# Adafruit_128x64_Mono_OLED_PCB_v2.net
KiCad netlist of a schematic drawn in EAGLE
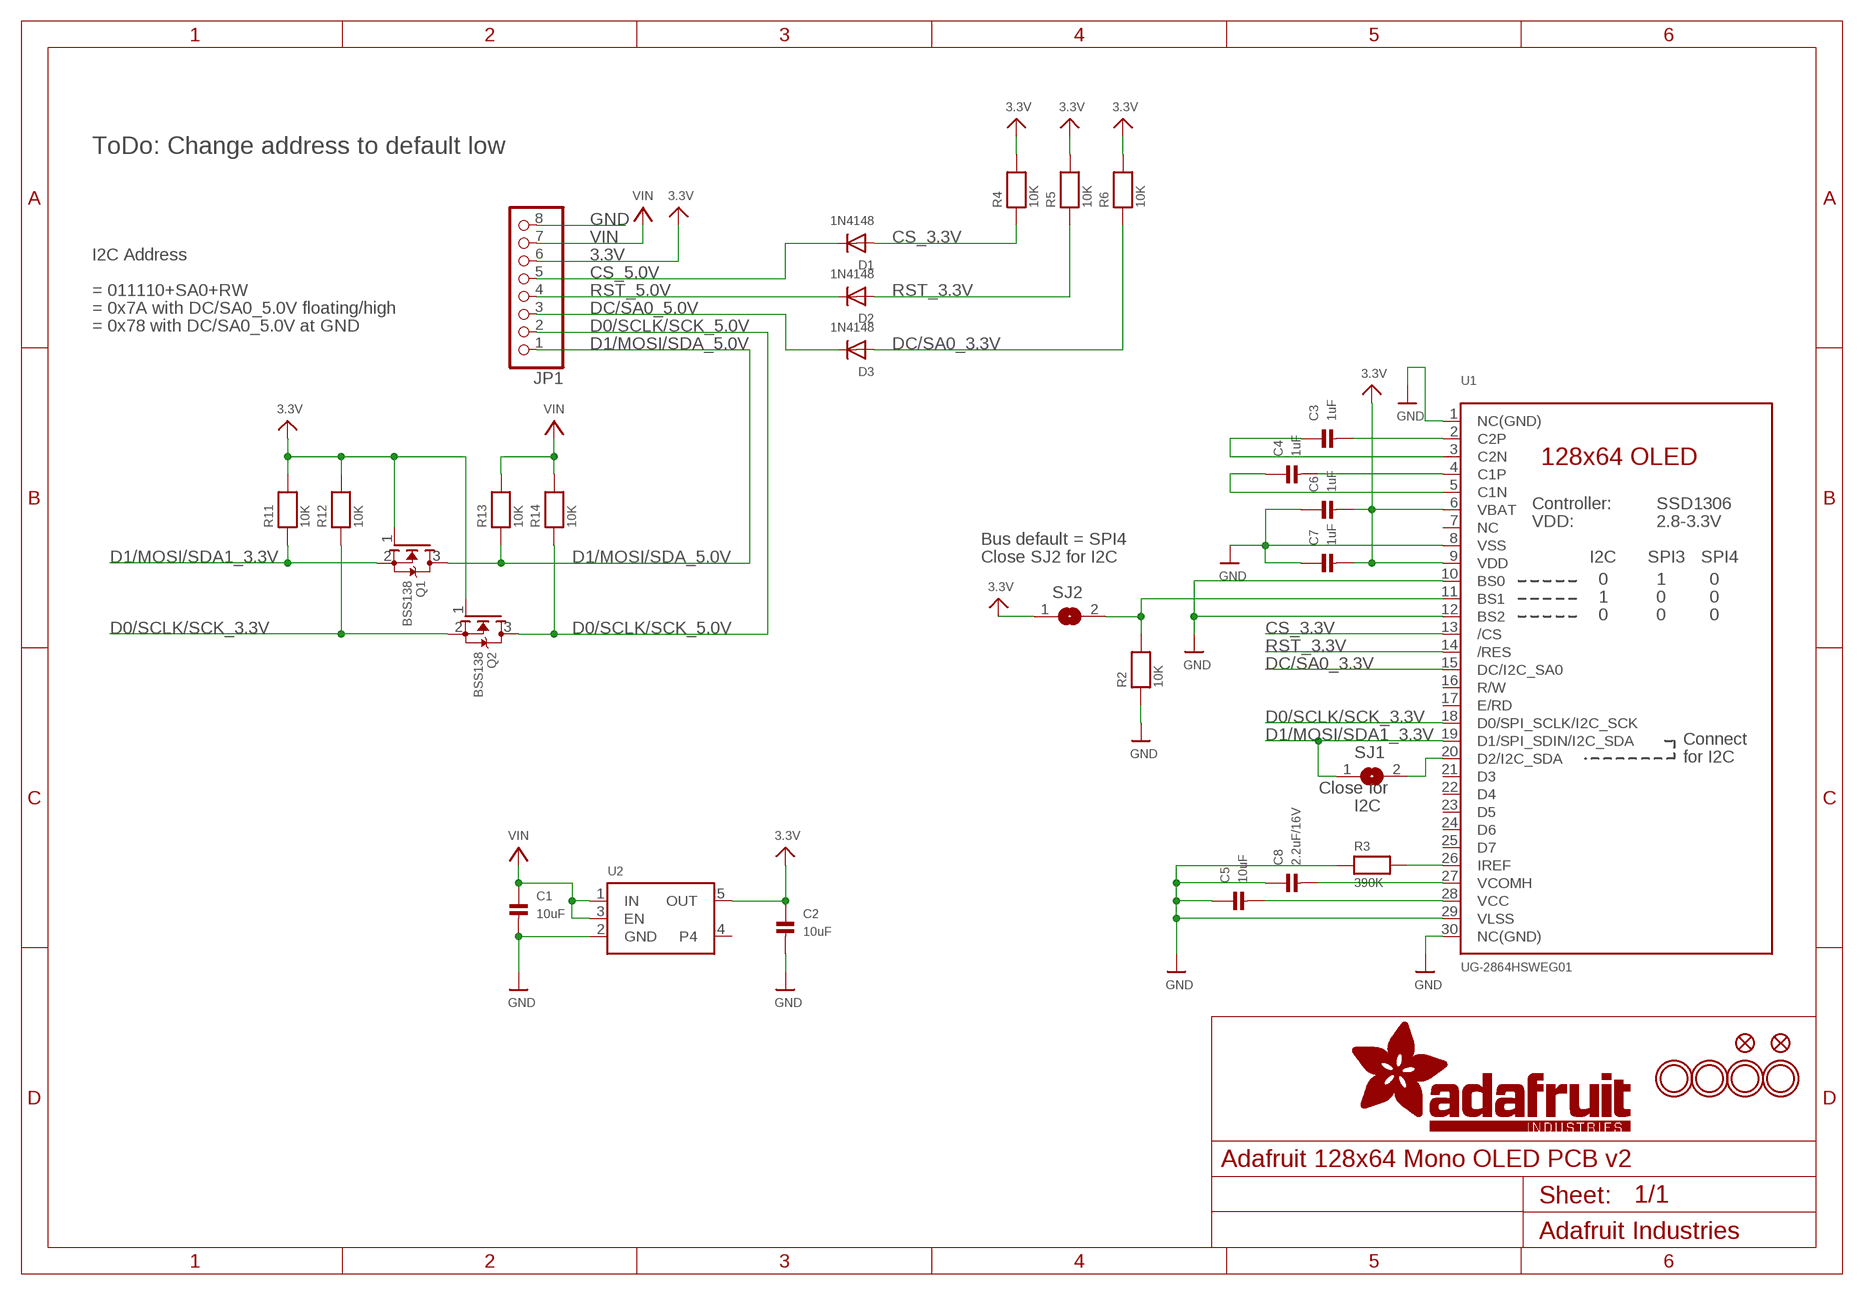
[diagram p0: schematic, sheet 1]

(export (version "E")
  (design (tool "Eeschema 10.0.6"))
  (components
    (comp (ref "C1")
      (value "10uF")
      (footprint "eagle-import:0805")
      (libsource (lib "eagle-import") (part "CAP_CERAMIC0805"))
    )
    (comp (ref "C2")
      (value "10uF")
      (footprint "eagle-import:0805")
      (libsource (lib "eagle-import") (part "CAP_CERAMIC0805"))
    )
    (comp (ref "C3")
      (value "1uF")
      (footprint "eagle-import:0805")
      (libsource (lib "eagle-import") (part "CAP_CERAMIC0805"))
    )
    (comp (ref "C4")
      (value "1uF")
      (footprint "eagle-import:0805")
      (libsource (lib "eagle-import") (part "CAP_CERAMIC0805"))
    )
    (comp (ref "C5")
      (value "10uF")
      (footprint "eagle-import:0805")
      (libsource (lib "eagle-import") (part "CAP_CERAMIC0805"))
    )
    (comp (ref "C6")
      (value "1uF")
      (footprint "eagle-import:0805")
      (libsource (lib "eagle-import") (part "CAP_CERAMIC0805"))
    )
    (comp (ref "C7")
      (value "1uF")
      (footprint "eagle-import:0805")
      (libsource (lib "eagle-import") (part "CAP_CERAMIC0805"))
    )
    (comp (ref "C8")
      (value "2.2uF/16V")
      (footprint "eagle-import:0805")
      (libsource (lib "eagle-import") (part "CAP_CERAMIC0805"))
    )
    (comp (ref "D1")
      (value "1N4148")
      (footprint "eagle-import:SOD-323")
      (libsource (lib "eagle-import") (part "DIODESOD-323"))
    )
    (comp (ref "D2")
      (value "1N4148")
      (footprint "eagle-import:SOD-323")
      (libsource (lib "eagle-import") (part "DIODESOD-323"))
    )
    (comp (ref "D3")
      (value "1N4148")
      (footprint "eagle-import:SOD-323")
      (libsource (lib "eagle-import") (part "DIODESOD-323"))
    )
    (comp (ref "FID1")
      (value "FIDUCIAL\"\"")
      (footprint "eagle-import:FIDUCIAL_1MM")
      (libsource (lib "eagle-import") (part "FIDUCIAL{dblquote}{dblquote}"))
    )
    (comp (ref "FID2")
      (value "FIDUCIAL\"\"")
      (footprint "eagle-import:FIDUCIAL_1MM")
      (libsource (lib "eagle-import") (part "FIDUCIAL{dblquote}{dblquote}"))
    )
    (comp (ref "JP1")
      (value "HEADER-1X870MIL")
      (footprint "eagle-import:1X08_ROUND_70")
      (libsource (lib "eagle-import") (part "HEADER-1X870MIL"))
    )
    (comp (ref "Q1")
      (value "BSS138")
      (footprint "eagle-import:SOT23-WIDE")
      (libsource (lib "eagle-import") (part "MOSFET-NWIDE"))
    )
    (comp (ref "Q2")
      (value "BSS138")
      (footprint "eagle-import:SOT23-WIDE")
      (libsource (lib "eagle-import") (part "MOSFET-NWIDE"))
    )
    (comp (ref "R2")
      (value "10K")
      (footprint "eagle-import:0805")
      (libsource (lib "eagle-import") (part "RESISTOR0805"))
    )
    (comp (ref "R3")
      (value "390K")
      (footprint "eagle-import:0805")
      (libsource (lib "eagle-import") (part "RESISTOR0805"))
    )
    (comp (ref "R4")
      (value "10K")
      (footprint "eagle-import:0805")
      (libsource (lib "eagle-import") (part "RESISTOR0805"))
    )
    (comp (ref "R5")
      (value "10K")
      (footprint "eagle-import:0805")
      (libsource (lib "eagle-import") (part "RESISTOR0805"))
    )
    (comp (ref "R6")
      (value "10K")
      (footprint "eagle-import:0805")
      (libsource (lib "eagle-import") (part "RESISTOR0805"))
    )
    (comp (ref "R11")
      (value "10K")
      (footprint "eagle-import:0805")
      (libsource (lib "eagle-import") (part "RESISTOR0805"))
    )
    (comp (ref "R12")
      (value "10K")
      (footprint "eagle-import:0805")
      (libsource (lib "eagle-import") (part "RESISTOR0805"))
    )
    (comp (ref "R13")
      (value "10K")
      (footprint "eagle-import:0805")
      (libsource (lib "eagle-import") (part "RESISTOR0805"))
    )
    (comp (ref "R14")
      (value "10K")
      (footprint "eagle-import:0805")
      (libsource (lib "eagle-import") (part "RESISTOR0805"))
    )
    (comp (ref "SJ1")
      (value "SOLDERJUMPERREFLOW_NOPASTE")
      (footprint "eagle-import:SOLDERJUMPER_REFLOW_NOPASTE")
      (libsource (lib "eagle-import") (part "SOLDERJUMPERREFLOW_NOPASTE"))
    )
    (comp (ref "SJ2")
      (value "SOLDERJUMPERREFLOW_NOPASTE")
      (footprint "eagle-import:SOLDERJUMPER_REFLOW_NOPASTE")
      (libsource (lib "eagle-import") (part "SOLDERJUMPERREFLOW_NOPASTE"))
    )
    (comp (ref "U$23")
      (value "MOUNTINGHOLE2.5")
      (footprint "eagle-import:MOUNTINGHOLE_2.5_PLATED")
      (libsource (lib "eagle-import") (part "MOUNTINGHOLE2.5"))
    )
    (comp (ref "U$24")
      (value "MOUNTINGHOLE2.5")
      (footprint "eagle-import:MOUNTINGHOLE_2.5_PLATED")
      (libsource (lib "eagle-import") (part "MOUNTINGHOLE2.5"))
    )
    (comp (ref "U$25")
      (value "MOUNTINGHOLE2.5")
      (footprint "eagle-import:MOUNTINGHOLE_2.5_PLATED")
      (libsource (lib "eagle-import") (part "MOUNTINGHOLE2.5"))
    )
    (comp (ref "U$26")
      (value "MOUNTINGHOLE2.5")
      (footprint "eagle-import:MOUNTINGHOLE_2.5_PLATED")
      (libsource (lib "eagle-import") (part "MOUNTINGHOLE2.5"))
    )
    (comp (ref "U1")
      (value "UG-2864HSWEG01")
      (footprint "eagle-import:UG-2864HSWEG01_0.96IN_WRAPAROUND")
      (libsource (lib "eagle-import") (part "DISP_OLED_UG-2864HSWEG010.96{dblquote}"))
    )
    (comp (ref "U2")
      (value "VREG_SOT23-5")
      (footprint "eagle-import:SOT23-5")
      (libsource (lib "eagle-import") (part "VREG_SOT23-5"))
    )
  )
  (nets
    (net (code "1") (name "/CS_3.3V") (class "Default")
      (node (ref "D1") (pin "A") (pinfunction "A_A") (pintype "passive"))
      (node (ref "R4") (pin "1") (pinfunction "1_1") (pintype "passive"))
      (node (ref "U1") (pin "13") (pinfunction "/CS_13") (pintype "input"))
    )
    (net (code "2") (name "/CS_5.0V") (class "Default")
      (node (ref "D1") (pin "C") (pinfunction "C_C") (pintype "passive"))
      (node (ref "JP1") (pin "5") (pinfunction "5_5") (pintype "passive"))
    )
    (net (code "3") (name "/D0{slash}SCLK{slash}SCK_3.3V") (class "Default")
      (node (ref "Q2") (pin "2") (pinfunction "S_2") (pintype "bidirectional"))
      (node (ref "R12") (pin "1") (pinfunction "1_1") (pintype "passive"))
      (node (ref "U1") (pin "18") (pinfunction "D0/SPI_SCLK/I2C_SCK_18") (pintype "bidirectional"))
    )
    (net (code "4") (name "/D0{slash}SCLK{slash}SCK_5.0V") (class "Default")
      (node (ref "JP1") (pin "2") (pinfunction "2_2") (pintype "passive"))
      (node (ref "Q2") (pin "3") (pinfunction "D_3") (pintype "bidirectional"))
      (node (ref "R14") (pin "1") (pinfunction "1_1") (pintype "passive"))
    )
    (net (code "5") (name "/D1{slash}MOSI{slash}SDA1_3.3V") (class "Default")
      (node (ref "Q1") (pin "2") (pinfunction "S_2") (pintype "bidirectional"))
      (node (ref "R11") (pin "1") (pinfunction "1_1") (pintype "passive"))
      (node (ref "SJ1") (pin "1") (pinfunction "1_1") (pintype "passive"))
      (node (ref "U1") (pin "19") (pinfunction "D1/SPI_SDIN/I2C_SDA_19") (pintype "bidirectional"))
    )
    (net (code "6") (name "/D1{slash}MOSI{slash}SDA_5.0V") (class "Default")
      (node (ref "JP1") (pin "1") (pinfunction "1_1") (pintype "passive"))
      (node (ref "Q1") (pin "3") (pinfunction "D_3") (pintype "bidirectional"))
      (node (ref "R13") (pin "1") (pinfunction "1_1") (pintype "passive"))
    )
    (net (code "7") (name "/DC{slash}SA0_3.3V") (class "Default")
      (node (ref "D3") (pin "A") (pinfunction "A_A") (pintype "passive"))
      (node (ref "R6") (pin "1") (pinfunction "1_1") (pintype "passive"))
      (node (ref "U1") (pin "15") (pinfunction "DC/I2C_SA0_15") (pintype "input"))
    )
    (net (code "8") (name "/DC{slash}SA0_5.0V") (class "Default")
      (node (ref "D3") (pin "C") (pinfunction "C_C") (pintype "passive"))
      (node (ref "JP1") (pin "3") (pinfunction "3_3") (pintype "passive"))
    )
    (net (code "9") (name "/RST_3.3V") (class "Default")
      (node (ref "D2") (pin "A") (pinfunction "A_A") (pintype "passive"))
      (node (ref "R5") (pin "1") (pinfunction "1_1") (pintype "passive"))
      (node (ref "U1") (pin "14") (pinfunction "/RES_14") (pintype "input"))
    )
    (net (code "10") (name "/RST_5.0V") (class "Default")
      (node (ref "D2") (pin "C") (pinfunction "C_C") (pintype "passive"))
      (node (ref "JP1") (pin "4") (pinfunction "4_4") (pintype "passive"))
    )
    (net (code "11") (name "3.3V") (class "Default")
      (node (ref "C2") (pin "1") (pinfunction "P$1_1") (pintype "passive"))
      (node (ref "C6") (pin "2") (pinfunction "P$2_2") (pintype "passive"))
      (node (ref "C7") (pin "2") (pinfunction "P$2_2") (pintype "passive"))
      (node (ref "JP1") (pin "6") (pinfunction "6_6") (pintype "passive"))
      (node (ref "Q1") (pin "1") (pinfunction "G_1") (pintype "bidirectional"))
      (node (ref "Q2") (pin "1") (pinfunction "G_1") (pintype "bidirectional"))
      (node (ref "R11") (pin "2") (pinfunction "2_2") (pintype "passive"))
      (node (ref "R12") (pin "2") (pinfunction "2_2") (pintype "passive"))
      (node (ref "R4") (pin "2") (pinfunction "2_2") (pintype "passive"))
      (node (ref "R5") (pin "2") (pinfunction "2_2") (pintype "passive"))
      (node (ref "R6") (pin "2") (pinfunction "2_2") (pintype "passive"))
      (node (ref "SJ2") (pin "1") (pinfunction "1_1") (pintype "passive"))
      (node (ref "U1") (pin "6") (pinfunction "VBAT_6") (pintype "input"))
      (node (ref "U1") (pin "9") (pinfunction "VDD_9") (pintype "power_in"))
      (node (ref "U2") (pin "5") (pinfunction "OUT_5") (pintype "bidirectional"))
    )
    (net (code "12") (name "GND") (class "Default")
      (node (ref "C1") (pin "2") (pinfunction "P$2_2") (pintype "passive"))
      (node (ref "C2") (pin "2") (pinfunction "P$2_2") (pintype "passive"))
      (node (ref "C5") (pin "1") (pinfunction "P$1_1") (pintype "passive"))
      (node (ref "C6") (pin "1") (pinfunction "P$1_1") (pintype "passive"))
      (node (ref "C7") (pin "1") (pinfunction "P$1_1") (pintype "passive"))
      (node (ref "C8") (pin "1") (pinfunction "P$1_1") (pintype "passive"))
      (node (ref "JP1") (pin "8") (pinfunction "8_8") (pintype "passive"))
      (node (ref "R2") (pin "1") (pinfunction "1_1") (pintype "passive"))
      (node (ref "R3") (pin "1") (pinfunction "1_1") (pintype "passive"))
      (node (ref "U1") (pin "1") (pinfunction "NC(GND)_1") (pintype "input"))
      (node (ref "U1") (pin "10") (pinfunction "BS0_10") (pintype "input"))
      (node (ref "U1") (pin "12") (pinfunction "BS2_12") (pintype "input"))
      (node (ref "U1") (pin "29") (pinfunction "VLSS_29") (pintype "power_in"))
      (node (ref "U1") (pin "30") (pinfunction "NC(GND)_30") (pintype "input"))
      (node (ref "U1") (pin "8") (pinfunction "VSS_8") (pintype "power_in"))
      (node (ref "U2") (pin "2") (pinfunction "GND_2") (pintype "bidirectional"))
    )
    (net (code "13") (name "Net-(C3-P$1)") (class "Default")
      (node (ref "C3") (pin "1") (pinfunction "P$1_1") (pintype "passive"))
      (node (ref "U1") (pin "3") (pinfunction "C2N_3") (pintype "input"))
    )
    (net (code "14") (name "Net-(C3-P$2)") (class "Default")
      (node (ref "C3") (pin "2") (pinfunction "P$2_2") (pintype "passive"))
      (node (ref "U1") (pin "2") (pinfunction "C2P_2") (pintype "input"))
    )
    (net (code "15") (name "Net-(C4-P$1)") (class "Default")
      (node (ref "C4") (pin "1") (pinfunction "P$1_1") (pintype "passive"))
      (node (ref "U1") (pin "5") (pinfunction "C1N_5") (pintype "input"))
    )
    (net (code "16") (name "Net-(C4-P$2)") (class "Default")
      (node (ref "C4") (pin "2") (pinfunction "P$2_2") (pintype "passive"))
      (node (ref "U1") (pin "4") (pinfunction "C1P_4") (pintype "input"))
    )
    (net (code "17") (name "Net-(C5-P$2)") (class "Default")
      (node (ref "C5") (pin "2") (pinfunction "P$2_2") (pintype "passive"))
      (node (ref "U1") (pin "28") (pinfunction "VCC_28") (pintype "power_in"))
    )
    (net (code "18") (name "Net-(C8-P$2)") (class "Default")
      (node (ref "C8") (pin "2") (pinfunction "P$2_2") (pintype "passive"))
      (node (ref "U1") (pin "27") (pinfunction "VCOMH_27") (pintype "output"))
    )
    (net (code "19") (name "Net-(U1-BS1)") (class "Default")
      (node (ref "R2") (pin "2") (pinfunction "2_2") (pintype "passive"))
      (node (ref "SJ2") (pin "2") (pinfunction "2_2") (pintype "passive"))
      (node (ref "U1") (pin "11") (pinfunction "BS1_11") (pintype "input"))
    )
    (net (code "20") (name "Net-(U1-D2{slash}I2C_SDA)") (class "Default")
      (node (ref "SJ1") (pin "2") (pinfunction "2_2") (pintype "passive"))
      (node (ref "U1") (pin "20") (pinfunction "D2/I2C_SDA_20") (pintype "bidirectional"))
    )
    (net (code "21") (name "Net-(U1-IREF)") (class "Default")
      (node (ref "R3") (pin "2") (pinfunction "2_2") (pintype "passive"))
      (node (ref "U1") (pin "26") (pinfunction "IREF_26") (pintype "input"))
    )
    (net (code "22") (name "VIN") (class "Default")
      (node (ref "C1") (pin "1") (pinfunction "P$1_1") (pintype "passive"))
      (node (ref "JP1") (pin "7") (pinfunction "7_7") (pintype "passive"))
      (node (ref "R13") (pin "2") (pinfunction "2_2") (pintype "passive"))
      (node (ref "R14") (pin "2") (pinfunction "2_2") (pintype "passive"))
      (node (ref "U2") (pin "1") (pinfunction "IN_1") (pintype "bidirectional"))
      (node (ref "U2") (pin "3") (pinfunction "EN_3") (pintype "bidirectional"))
    )
    (net (code "23") (name "unconnected-(U1-D3-Pad21)") (class "Default")
      (node (ref "U1") (pin "21") (pinfunction "D3_21") (pintype "bidirectional"))
    )
    (net (code "24") (name "unconnected-(U1-D4-Pad22)") (class "Default")
      (node (ref "U1") (pin "22") (pinfunction "D4_22") (pintype "bidirectional"))
    )
    (net (code "25") (name "unconnected-(U1-D5-Pad23)") (class "Default")
      (node (ref "U1") (pin "23") (pinfunction "D5_23") (pintype "bidirectional"))
    )
    (net (code "26") (name "unconnected-(U1-D6-Pad24)") (class "Default")
      (node (ref "U1") (pin "24") (pinfunction "D6_24") (pintype "bidirectional"))
    )
    (net (code "27") (name "unconnected-(U1-D7-Pad25)") (class "Default")
      (node (ref "U1") (pin "25") (pinfunction "D7_25") (pintype "bidirectional"))
    )
    (net (code "28") (name "unconnected-(U1-E{slash}RD-Pad17)") (class "Default")
      (node (ref "U1") (pin "17") (pinfunction "E/RD_17") (pintype "input"))
    )
    (net (code "29") (name "unconnected-(U1-NC-Pad7)") (class "Default")
      (node (ref "U1") (pin "7") (pinfunction "NC_7") (pintype "no_connect"))
    )
    (net (code "30") (name "unconnected-(U1-R{slash}W-Pad16)") (class "Default")
      (node (ref "U1") (pin "16") (pinfunction "R/W_16") (pintype "input"))
    )
    (net (code "31") (name "unconnected-(U2-P4-Pad4)") (class "Default")
      (node (ref "U2") (pin "4") (pinfunction "P4_4") (pintype "bidirectional"))
    )
  )
)
